# Headers_Power.net
KiCad netlist of a schematic drawn in Altium Designer
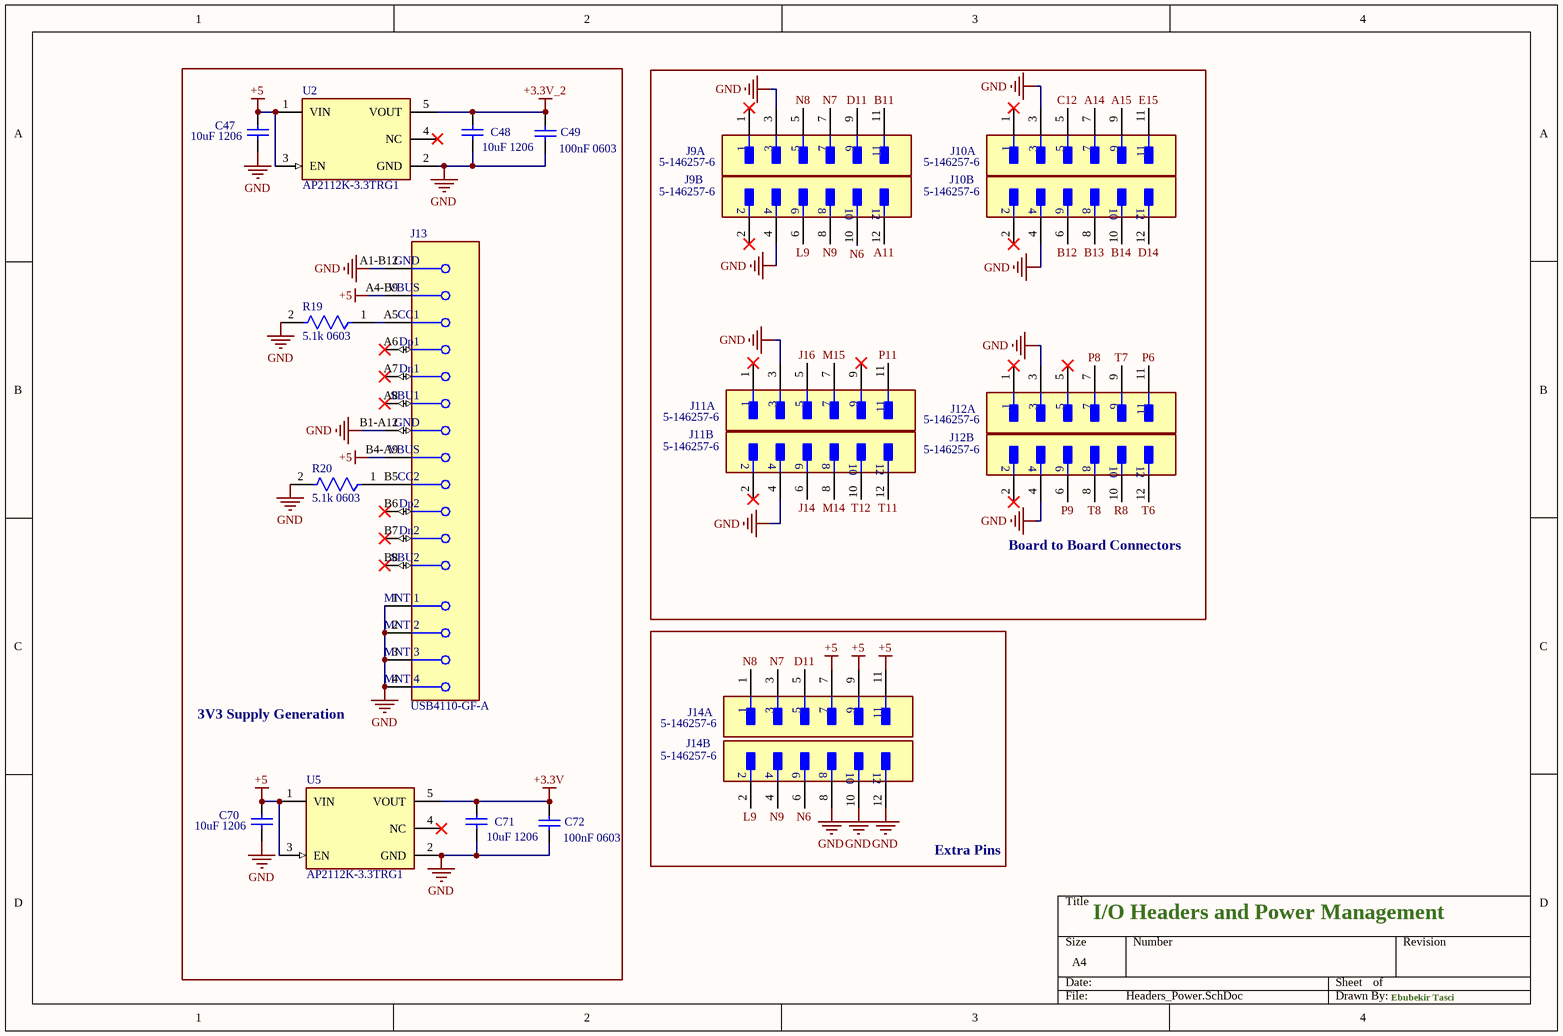
[diagram p0: Headers_Power.SchDoc]

(export (version "E")
  (design (tool "Eeschema 10.0.6"))
  (components
    (comp (ref "C47")
      (value "10uF 1206")
      (footprint "CAPC1206(3216)190_M")
      (description "CAP 10uF 16V ±5% 1206 (3216 Metric) Thickness 1.9mm SMD")
      (fields (field (name "TOLERANCE") "Â±5%"))
      (libsource (lib "Altium Content Vault") (part "CAP"))
    )
    (comp (ref "C48")
      (value "10uF 1206")
      (footprint "CAPC1206(3216)190_M")
      (description "CAP 10uF 16V ±5% 1206 (3216 Metric) Thickness 1.9mm SMD")
      (fields (field (name "TOLERANCE") "Â±5%"))
      (libsource (lib "Altium Content Vault") (part "CAP"))
    )
    (comp (ref "C49")
      (value "100nF 0603")
      (footprint "CAPC0603(1608)100_L")
      (description "CAP 100nF 16V ±0.1pF 0603 (1608 Metric) Thickness 1mm SMD")
      (fields (field (name "TOLERANCE") "Â±0.1pF"))
      (libsource (lib "Altium Content Vault") (part "CAP"))
    )
    (comp (ref "C70")
      (value "10uF 1206")
      (footprint "CAPC1206(3216)190_M")
      (description "CAP 10uF 16V ±5% 1206 (3216 Metric) Thickness 1.9mm SMD")
      (fields (field (name "TOLERANCE") "Â±5%"))
      (libsource (lib "Altium Content Vault") (part "CAP"))
    )
    (comp (ref "C71")
      (value "10uF 1206")
      (footprint "CAPC1206(3216)190_M")
      (description "CAP 10uF 16V ±5% 1206 (3216 Metric) Thickness 1.9mm SMD")
      (fields (field (name "TOLERANCE") "Â±5%"))
      (libsource (lib "Altium Content Vault") (part "CAP"))
    )
    (comp (ref "C72")
      (value "100nF 0603")
      (footprint "CAPC0603(1608)100_L")
      (description "CAP 100nF 16V ±0.1pF 0603 (1608 Metric) Thickness 1mm SMD")
      (fields (field (name "TOLERANCE") "Â±0.1pF"))
      (libsource (lib "Altium Content Vault") (part "CAP"))
    )
    (comp (ref "J9")
      (value "5-146257-6")
      (footprint "FP-5-146257-6-MFG")
      (description "CONN HEADER VERT 12POS 2.54MM")
      (libsource (lib "") (part "803cea653fbe7ecf087c1bc3cef566d_1"))
    )
    (comp (ref "J10")
      (value "5-146257-6")
      (footprint "FP-5-146257-6-MFG")
      (description "CONN HEADER VERT 12POS 2.54MM")
      (libsource (lib "") (part "803cea653fbe7ecf087c1bc3cef566d_1"))
    )
    (comp (ref "J11")
      (value "5-146257-6")
      (footprint "FP-5-146257-6-MFG")
      (description "CONN HEADER VERT 12POS 2.54MM")
      (libsource (lib "") (part "803cea653fbe7ecf087c1bc3cef566d_1"))
    )
    (comp (ref "J12")
      (value "5-146257-6")
      (footprint "FP-5-146257-6-MFG")
      (description "CONN HEADER VERT 12POS 2.54MM")
      (libsource (lib "") (part "803cea653fbe7ecf087c1bc3cef566d_1"))
    )
    (comp (ref "J13")
      (value "USB4110-GF-A")
      (footprint "FP-USB4110-GF-A-MFG")
      (description "CONN USB 2.0 TYPE-C R/A SMT")
      (fields
        (field (name "OCTOPART") "https://octopart.com/usb4110-gf-a-gct-103941985")
        (field (name "MANUFACTURER") "GCT")
      )
      (libsource (lib "Altium Content Vault") (part "e23f2b38bb3c3f98e683ebab9ede730"))
    )
    (comp (ref "J14")
      (value "5-146257-6")
      (footprint "FP-5-146257-6-MFG")
      (description "CONN HEADER VERT 12POS 2.54MM")
      (libsource (lib "") (part "803cea653fbe7ecf087c1bc3cef566d_1"))
    )
    (comp (ref "R19")
      (value "5.1k 0603")
      (footprint "FP-MCT0603-IPC_A")
      (description "RES SMD 5.1 KOHM 1% 1/8W 0603")
      (fields (field (name "TOLERANCE") "1%"))
      (libsource (lib "Altium Content Vault") (part "1029c3af85768c4190bb7ad29bc67b5"))
    )
    (comp (ref "R20")
      (value "5.1k 0603")
      (footprint "FP-MCT0603-IPC_A")
      (description "RES SMD 5.1 KOHM 1% 1/8W 0603")
      (fields (field (name "TOLERANCE") "1%"))
      (libsource (lib "Altium Content Vault") (part "1029c3af85768c4190bb7ad29bc67b5"))
    )
    (comp (ref "U2")
      (value "AP2112K-3.3TRG1")
      (footprint "FP-SOT25-IPC_A")
      (description "IC REG LINEAR 3.3V 600MA SOT25")
      (libsource (lib "Altium Content Vault") (part "c8ab751aee5229183125ab046a11caa"))
    )
    (comp (ref "U5")
      (value "AP2112K-3.3TRG1")
      (footprint "FP-SOT25-IPC_A")
      (description "IC REG LINEAR 3.3V 600MA SOT25")
      (libsource (lib "Altium Content Vault") (part "c8ab751aee5229183125ab046a11caa"))
    )
  )
  (nets
    (net (code "1") (name "+3.3V") (class "Default")
      (node (ref "C71") (pin "2") (pinfunction "2_2") (pintype "passive"))
      (node (ref "C72") (pin "1") (pinfunction "1_1") (pintype "passive"))
      (node (ref "U5") (pin "5") (pinfunction "VOUT_5") (pintype "power_in"))
    )
    (net (code "2") (name "+3.3V_2") (class "Default")
      (node (ref "C48") (pin "2") (pinfunction "2_2") (pintype "passive"))
      (node (ref "C49") (pin "1") (pinfunction "1_1") (pintype "passive"))
      (node (ref "U2") (pin "5") (pinfunction "VOUT_5") (pintype "power_in"))
    )
    (net (code "3") (name "+5") (class "Default")
      (node (ref "C47") (pin "2") (pinfunction "2_2") (pintype "passive"))
      (node (ref "C70") (pin "2") (pinfunction "2_2") (pintype "passive"))
      (node (ref "J13") (pin "A4-B9") (pinfunction "VBUS_A4-B9") (pintype "power_in"))
      (node (ref "J13") (pin "B4-A9") (pinfunction "VBUS_B4-A9") (pintype "power_in"))
      (node (ref "J14") (pin "11") (pinfunction "11_11") (pintype "passive"))
      (node (ref "J14") (pin "7") (pinfunction "7_7") (pintype "passive"))
      (node (ref "J14") (pin "9") (pinfunction "9_9") (pintype "passive"))
      (node (ref "U2") (pin "1") (pinfunction "VIN_1") (pintype "power_in"))
      (node (ref "U2") (pin "3") (pinfunction "EN_3") (pintype "input"))
      (node (ref "U5") (pin "1") (pinfunction "VIN_1") (pintype "power_in"))
      (node (ref "U5") (pin "3") (pinfunction "EN_3") (pintype "input"))
    )
    (net (code "4") (name "/A11") (class "Default")
      (node (ref "J9") (pin "12") (pinfunction "12_12") (pintype "passive"))
    )
    (net (code "5") (name "/A14") (class "Default")
      (node (ref "J10") (pin "7") (pinfunction "7_7") (pintype "passive"))
    )
    (net (code "6") (name "/A15") (class "Default")
      (node (ref "J10") (pin "9") (pinfunction "9_9") (pintype "passive"))
    )
    (net (code "7") (name "/B11") (class "Default")
      (node (ref "J9") (pin "11") (pinfunction "11_11") (pintype "passive"))
    )
    (net (code "8") (name "/B12") (class "Default")
      (node (ref "J10") (pin "6") (pinfunction "6_6") (pintype "passive"))
    )
    (net (code "9") (name "/B13") (class "Default")
      (node (ref "J10") (pin "8") (pinfunction "8_8") (pintype "passive"))
    )
    (net (code "10") (name "/B14") (class "Default")
      (node (ref "J10") (pin "10") (pinfunction "10_10") (pintype "passive"))
    )
    (net (code "11") (name "/C12") (class "Default")
      (node (ref "J10") (pin "5") (pinfunction "5_5") (pintype "passive"))
    )
    (net (code "12") (name "/D11") (class "Default")
      (node (ref "J14") (pin "5") (pinfunction "5_5") (pintype "passive"))
      (node (ref "J9") (pin "9") (pinfunction "9_9") (pintype "passive"))
    )
    (net (code "13") (name "/D14") (class "Default")
      (node (ref "J10") (pin "12") (pinfunction "12_12") (pintype "passive"))
    )
    (net (code "14") (name "/E15") (class "Default")
      (node (ref "J10") (pin "11") (pinfunction "11_11") (pintype "passive"))
    )
    (net (code "15") (name "/J14") (class "Default")
      (node (ref "J11") (pin "6") (pinfunction "6_6") (pintype "passive"))
    )
    (net (code "16") (name "/J16") (class "Default")
      (node (ref "J11") (pin "5") (pinfunction "5_5") (pintype "passive"))
    )
    (net (code "17") (name "/L9") (class "Default")
      (node (ref "J14") (pin "2") (pinfunction "2_2") (pintype "passive"))
      (node (ref "J9") (pin "6") (pinfunction "6_6") (pintype "passive"))
    )
    (net (code "18") (name "/M14") (class "Default")
      (node (ref "J11") (pin "8") (pinfunction "8_8") (pintype "passive"))
    )
    (net (code "19") (name "/M15") (class "Default")
      (node (ref "J11") (pin "7") (pinfunction "7_7") (pintype "passive"))
    )
    (net (code "20") (name "/N6") (class "Default")
      (node (ref "J14") (pin "6") (pinfunction "6_6") (pintype "passive"))
      (node (ref "J9") (pin "10") (pinfunction "10_10") (pintype "passive"))
    )
    (net (code "21") (name "/N7") (class "Default")
      (node (ref "J14") (pin "3") (pinfunction "3_3") (pintype "passive"))
      (node (ref "J9") (pin "7") (pinfunction "7_7") (pintype "passive"))
    )
    (net (code "22") (name "/N8") (class "Default")
      (node (ref "J14") (pin "1") (pinfunction "1_1") (pintype "passive"))
      (node (ref "J9") (pin "5") (pinfunction "5_5") (pintype "passive"))
    )
    (net (code "23") (name "/N9") (class "Default")
      (node (ref "J14") (pin "4") (pinfunction "4_4") (pintype "passive"))
      (node (ref "J9") (pin "8") (pinfunction "8_8") (pintype "passive"))
    )
    (net (code "24") (name "/P6") (class "Default")
      (node (ref "J12") (pin "11") (pinfunction "11_11") (pintype "passive"))
    )
    (net (code "25") (name "/P8") (class "Default")
      (node (ref "J12") (pin "7") (pinfunction "7_7") (pintype "passive"))
    )
    (net (code "26") (name "/P9") (class "Default")
      (node (ref "J12") (pin "6") (pinfunction "6_6") (pintype "passive"))
    )
    (net (code "27") (name "/P11") (class "Default")
      (node (ref "J11") (pin "11") (pinfunction "11_11") (pintype "passive"))
    )
    (net (code "28") (name "/R8") (class "Default")
      (node (ref "J12") (pin "10") (pinfunction "10_10") (pintype "passive"))
    )
    (net (code "29") (name "/T6") (class "Default")
      (node (ref "J12") (pin "12") (pinfunction "12_12") (pintype "passive"))
    )
    (net (code "30") (name "/T7") (class "Default")
      (node (ref "J12") (pin "9") (pinfunction "9_9") (pintype "passive"))
    )
    (net (code "31") (name "/T8") (class "Default")
      (node (ref "J12") (pin "8") (pinfunction "8_8") (pintype "passive"))
    )
    (net (code "32") (name "/T11") (class "Default")
      (node (ref "J11") (pin "12") (pinfunction "12_12") (pintype "passive"))
    )
    (net (code "33") (name "/T12") (class "Default")
      (node (ref "J11") (pin "10") (pinfunction "10_10") (pintype "passive"))
    )
    (net (code "34") (name "GND") (class "Default")
      (node (ref "C47") (pin "1") (pinfunction "1_1") (pintype "passive"))
      (node (ref "C48") (pin "1") (pinfunction "1_1") (pintype "passive"))
      (node (ref "C49") (pin "2") (pinfunction "2_2") (pintype "passive"))
      (node (ref "C70") (pin "1") (pinfunction "1_1") (pintype "passive"))
      (node (ref "C71") (pin "1") (pinfunction "1_1") (pintype "passive"))
      (node (ref "C72") (pin "2") (pinfunction "2_2") (pintype "passive"))
      (node (ref "J10") (pin "3") (pinfunction "3_3") (pintype "passive"))
      (node (ref "J10") (pin "4") (pinfunction "4_4") (pintype "passive"))
      (node (ref "J11") (pin "3") (pinfunction "3_3") (pintype "passive"))
      (node (ref "J11") (pin "4") (pinfunction "4_4") (pintype "passive"))
      (node (ref "J12") (pin "3") (pinfunction "3_3") (pintype "passive"))
      (node (ref "J12") (pin "4") (pinfunction "4_4") (pintype "passive"))
      (node (ref "J13") (pin "1") (pinfunction "MNT_1_1") (pintype "passive"))
      (node (ref "J13") (pin "2") (pinfunction "MNT_2_2") (pintype "passive"))
      (node (ref "J13") (pin "3") (pinfunction "MNT_3_3") (pintype "passive"))
      (node (ref "J13") (pin "4") (pinfunction "MNT_4_4") (pintype "passive"))
      (node (ref "J13") (pin "A1-B12") (pinfunction "GND_A1-B12") (pintype "passive"))
      (node (ref "J13") (pin "B1-A12") (pinfunction "GND_B1-A12") (pintype "bidirectional"))
      (node (ref "J14") (pin "10") (pinfunction "10_10") (pintype "passive"))
      (node (ref "J14") (pin "12") (pinfunction "12_12") (pintype "passive"))
      (node (ref "J14") (pin "8") (pinfunction "8_8") (pintype "passive"))
      (node (ref "J9") (pin "3") (pinfunction "3_3") (pintype "passive"))
      (node (ref "J9") (pin "4") (pinfunction "4_4") (pintype "passive"))
      (node (ref "R19") (pin "2") (pinfunction "2_2") (pintype "passive"))
      (node (ref "R20") (pin "2") (pinfunction "2_2") (pintype "passive"))
      (node (ref "U2") (pin "2") (pinfunction "GND_2") (pintype "power_in"))
      (node (ref "U5") (pin "2") (pinfunction "GND_2") (pintype "power_in"))
    )
    (net (code "35") (name "Net-(J13-CC1)") (class "Default")
      (node (ref "J13") (pin "A5") (pinfunction "CC1_A5") (pintype "power_in"))
      (node (ref "R19") (pin "1") (pinfunction "1_1") (pintype "passive"))
    )
    (net (code "36") (name "Net-(J13-CC2)") (class "Default")
      (node (ref "J13") (pin "B5") (pinfunction "CC2_B5") (pintype "power_in"))
      (node (ref "R20") (pin "1") (pinfunction "1_1") (pintype "passive"))
    )
    (net (code "37") (name "unconnected-(J9-Pad1)") (class "Default")
      (node (ref "J9") (pin "1") (pinfunction "1_1") (pintype "passive+no_connect"))
    )
    (net (code "38") (name "unconnected-(J9-Pad2)") (class "Default")
      (node (ref "J9") (pin "2") (pinfunction "2_2") (pintype "passive+no_connect"))
    )
    (net (code "39") (name "unconnected-(J10-Pad1)") (class "Default")
      (node (ref "J10") (pin "1") (pinfunction "1_1") (pintype "passive+no_connect"))
    )
    (net (code "40") (name "unconnected-(J10-Pad2)") (class "Default")
      (node (ref "J10") (pin "2") (pinfunction "2_2") (pintype "passive+no_connect"))
    )
    (net (code "41") (name "unconnected-(J11-Pad1)") (class "Default")
      (node (ref "J11") (pin "1") (pinfunction "1_1") (pintype "passive+no_connect"))
    )
    (net (code "42") (name "unconnected-(J11-Pad2)") (class "Default")
      (node (ref "J11") (pin "2") (pinfunction "2_2") (pintype "passive+no_connect"))
    )
    (net (code "43") (name "unconnected-(J11-Pad9)") (class "Default")
      (node (ref "J11") (pin "9") (pinfunction "9_9") (pintype "passive+no_connect"))
    )
    (net (code "44") (name "unconnected-(J12-Pad1)") (class "Default")
      (node (ref "J12") (pin "1") (pinfunction "1_1") (pintype "passive+no_connect"))
    )
    (net (code "45") (name "unconnected-(J12-Pad2)") (class "Default")
      (node (ref "J12") (pin "2") (pinfunction "2_2") (pintype "passive+no_connect"))
    )
    (net (code "46") (name "unconnected-(J12-Pad5)") (class "Default")
      (node (ref "J12") (pin "5") (pinfunction "5_5") (pintype "passive+no_connect"))
    )
    (net (code "47") (name "unconnected-(J13-Dn1-PadA7)") (class "Default")
      (node (ref "J13") (pin "A7") (pinfunction "Dn1_A7") (pintype "bidirectional+no_connect"))
    )
    (net (code "48") (name "unconnected-(J13-Dn2-PadB7)") (class "Default")
      (node (ref "J13") (pin "B7") (pinfunction "Dn2_B7") (pintype "bidirectional+no_connect"))
    )
    (net (code "49") (name "unconnected-(J13-Dp1-PadA6)") (class "Default")
      (node (ref "J13") (pin "A6") (pinfunction "Dp1_A6") (pintype "bidirectional+no_connect"))
    )
    (net (code "50") (name "unconnected-(J13-Dp2-PadB6)") (class "Default")
      (node (ref "J13") (pin "B6") (pinfunction "Dp2_B6") (pintype "bidirectional+no_connect"))
    )
    (net (code "51") (name "unconnected-(J13-SBU1-PadA8)") (class "Default")
      (node (ref "J13") (pin "A8") (pinfunction "SBU1_A8") (pintype "bidirectional+no_connect"))
    )
    (net (code "52") (name "unconnected-(J13-SBU2-PadB8)") (class "Default")
      (node (ref "J13") (pin "B8") (pinfunction "SBU2_B8") (pintype "bidirectional+no_connect"))
    )
    (net (code "53") (name "unconnected-(U2-NC-Pad4)") (class "Default")
      (node (ref "U2") (pin "4") (pinfunction "NC_4") (pintype "passive+no_connect"))
    )
    (net (code "54") (name "unconnected-(U5-NC-Pad4)") (class "Default")
      (node (ref "U5") (pin "4") (pinfunction "NC_4") (pintype "passive+no_connect"))
    )
  )
)
